# LAD_1_0.net
KiCad netlist of a schematic drawn in EAGLE
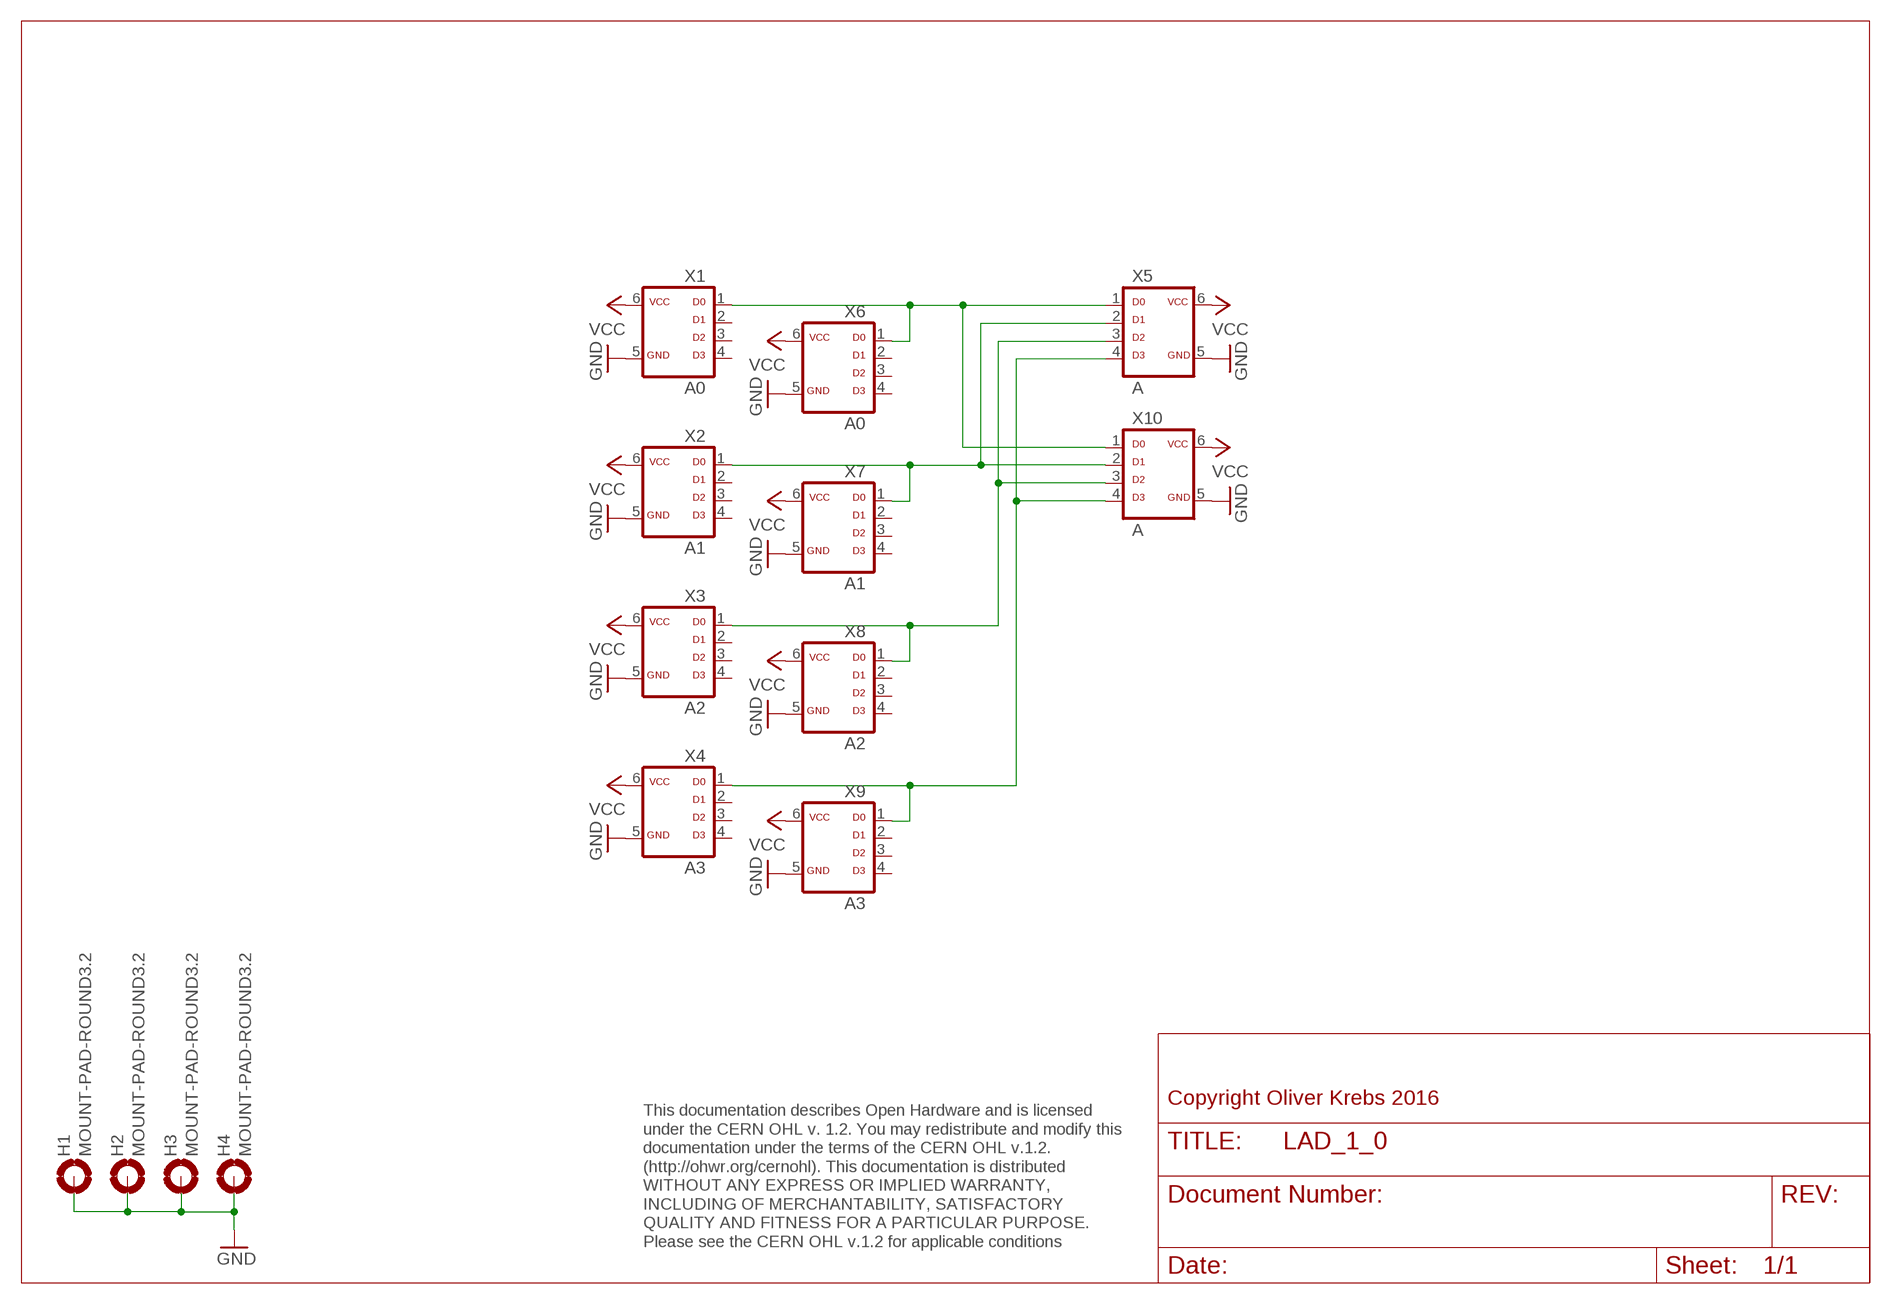
[diagram p0: schematic, sheet 1]

(export (version "E")
  (design (tool "Eeschema 10.0.6"))
  (components
    (comp (ref "H1")
      (value "MOUNT-PAD-ROUND3.2")
      (footprint "eagle-import:3,2-PAD")
      (libsource (lib "eagle-import") (part "MOUNT-PAD-ROUND3.2"))
    )
    (comp (ref "H2")
      (value "MOUNT-PAD-ROUND3.2")
      (footprint "eagle-import:3,2-PAD")
      (libsource (lib "eagle-import") (part "MOUNT-PAD-ROUND3.2"))
    )
    (comp (ref "H3")
      (value "MOUNT-PAD-ROUND3.2")
      (footprint "eagle-import:3,2-PAD")
      (libsource (lib "eagle-import") (part "MOUNT-PAD-ROUND3.2"))
    )
    (comp (ref "H4")
      (value "MOUNT-PAD-ROUND3.2")
      (footprint "eagle-import:3,2-PAD")
      (libsource (lib "eagle-import") (part "MOUNT-PAD-ROUND3.2"))
    )
    (comp (ref "X1")
      (value "A0")
      (footprint "eagle-import:ML-6")
      (libsource (lib "eagle-import") (part "ML6D"))
    )
    (comp (ref "X2")
      (value "A1")
      (footprint "eagle-import:ML-6")
      (libsource (lib "eagle-import") (part "ML6D"))
    )
    (comp (ref "X3")
      (value "A2")
      (footprint "eagle-import:ML-6")
      (libsource (lib "eagle-import") (part "ML6D"))
    )
    (comp (ref "X4")
      (value "A3")
      (footprint "eagle-import:ML-6")
      (libsource (lib "eagle-import") (part "ML6D"))
    )
    (comp (ref "X5")
      (value "A")
      (footprint "eagle-import:ML-6")
      (libsource (lib "eagle-import") (part "ML6D"))
    )
    (comp (ref "X6")
      (value "A0")
      (footprint "eagle-import:ML-6")
      (libsource (lib "eagle-import") (part "ML6D"))
    )
    (comp (ref "X7")
      (value "A1")
      (footprint "eagle-import:ML-6")
      (libsource (lib "eagle-import") (part "ML6D"))
    )
    (comp (ref "X8")
      (value "A2")
      (footprint "eagle-import:ML-6")
      (libsource (lib "eagle-import") (part "ML6D"))
    )
    (comp (ref "X9")
      (value "A3")
      (footprint "eagle-import:ML-6")
      (libsource (lib "eagle-import") (part "ML6D"))
    )
    (comp (ref "X10")
      (value "A")
      (footprint "eagle-import:ML-6")
      (libsource (lib "eagle-import") (part "ML6D"))
    )
  )
  (nets
    (net (code "1") (name "GND") (class "Default")
      (node (ref "H1") (pin "B3,2") (pinfunction "MOUNT_B3,2") (pintype "passive"))
      (node (ref "H2") (pin "B3,2") (pinfunction "MOUNT_B3,2") (pintype "passive"))
      (node (ref "H3") (pin "B3,2") (pinfunction "MOUNT_B3,2") (pintype "passive"))
      (node (ref "H4") (pin "B3,2") (pinfunction "MOUNT_B3,2") (pintype "passive"))
      (node (ref "X1") (pin "5") (pinfunction "5_5") (pintype "passive"))
      (node (ref "X10") (pin "5") (pinfunction "5_5") (pintype "passive"))
      (node (ref "X2") (pin "5") (pinfunction "5_5") (pintype "passive"))
      (node (ref "X3") (pin "5") (pinfunction "5_5") (pintype "passive"))
      (node (ref "X4") (pin "5") (pinfunction "5_5") (pintype "passive"))
      (node (ref "X5") (pin "5") (pinfunction "5_5") (pintype "passive"))
      (node (ref "X6") (pin "5") (pinfunction "5_5") (pintype "passive"))
      (node (ref "X7") (pin "5") (pinfunction "5_5") (pintype "passive"))
      (node (ref "X8") (pin "5") (pinfunction "5_5") (pintype "passive"))
      (node (ref "X9") (pin "5") (pinfunction "5_5") (pintype "passive"))
    )
    (net (code "2") (name "Net-(X1-Pad1)") (class "Default")
      (node (ref "X1") (pin "1") (pinfunction "1_1") (pintype "passive"))
      (node (ref "X10") (pin "1") (pinfunction "1_1") (pintype "passive"))
      (node (ref "X5") (pin "1") (pinfunction "1_1") (pintype "passive"))
      (node (ref "X6") (pin "1") (pinfunction "1_1") (pintype "passive"))
    )
    (net (code "3") (name "Net-(X10-Pad2)") (class "Default")
      (node (ref "X10") (pin "2") (pinfunction "2_2") (pintype "passive"))
      (node (ref "X2") (pin "1") (pinfunction "1_1") (pintype "passive"))
      (node (ref "X5") (pin "2") (pinfunction "2_2") (pintype "passive"))
      (node (ref "X7") (pin "1") (pinfunction "1_1") (pintype "passive"))
    )
    (net (code "4") (name "Net-(X10-Pad3)") (class "Default")
      (node (ref "X10") (pin "3") (pinfunction "3_3") (pintype "passive"))
      (node (ref "X3") (pin "1") (pinfunction "1_1") (pintype "passive"))
      (node (ref "X5") (pin "3") (pinfunction "3_3") (pintype "passive"))
      (node (ref "X8") (pin "1") (pinfunction "1_1") (pintype "passive"))
    )
    (net (code "5") (name "Net-(X10-Pad4)") (class "Default")
      (node (ref "X10") (pin "4") (pinfunction "4_4") (pintype "passive"))
      (node (ref "X4") (pin "1") (pinfunction "1_1") (pintype "passive"))
      (node (ref "X5") (pin "4") (pinfunction "4_4") (pintype "passive"))
      (node (ref "X9") (pin "1") (pinfunction "1_1") (pintype "passive"))
    )
    (net (code "6") (name "VCC") (class "Default")
      (node (ref "X1") (pin "6") (pinfunction "6_6") (pintype "passive"))
      (node (ref "X10") (pin "6") (pinfunction "6_6") (pintype "passive"))
      (node (ref "X2") (pin "6") (pinfunction "6_6") (pintype "passive"))
      (node (ref "X3") (pin "6") (pinfunction "6_6") (pintype "passive"))
      (node (ref "X4") (pin "6") (pinfunction "6_6") (pintype "passive"))
      (node (ref "X5") (pin "6") (pinfunction "6_6") (pintype "passive"))
      (node (ref "X6") (pin "6") (pinfunction "6_6") (pintype "passive"))
      (node (ref "X7") (pin "6") (pinfunction "6_6") (pintype "passive"))
      (node (ref "X8") (pin "6") (pinfunction "6_6") (pintype "passive"))
      (node (ref "X9") (pin "6") (pinfunction "6_6") (pintype "passive"))
    )
    (net (code "7") (name "unconnected-(X1-Pad2)") (class "Default")
      (node (ref "X1") (pin "2") (pinfunction "2_2") (pintype "passive"))
    )
    (net (code "8") (name "unconnected-(X1-Pad3)") (class "Default")
      (node (ref "X1") (pin "3") (pinfunction "3_3") (pintype "passive"))
    )
    (net (code "9") (name "unconnected-(X1-Pad4)") (class "Default")
      (node (ref "X1") (pin "4") (pinfunction "4_4") (pintype "passive"))
    )
    (net (code "10") (name "unconnected-(X2-Pad2)") (class "Default")
      (node (ref "X2") (pin "2") (pinfunction "2_2") (pintype "passive"))
    )
    (net (code "11") (name "unconnected-(X2-Pad3)") (class "Default")
      (node (ref "X2") (pin "3") (pinfunction "3_3") (pintype "passive"))
    )
    (net (code "12") (name "unconnected-(X2-Pad4)") (class "Default")
      (node (ref "X2") (pin "4") (pinfunction "4_4") (pintype "passive"))
    )
    (net (code "13") (name "unconnected-(X3-Pad2)") (class "Default")
      (node (ref "X3") (pin "2") (pinfunction "2_2") (pintype "passive"))
    )
    (net (code "14") (name "unconnected-(X3-Pad3)") (class "Default")
      (node (ref "X3") (pin "3") (pinfunction "3_3") (pintype "passive"))
    )
    (net (code "15") (name "unconnected-(X3-Pad4)") (class "Default")
      (node (ref "X3") (pin "4") (pinfunction "4_4") (pintype "passive"))
    )
    (net (code "16") (name "unconnected-(X4-Pad2)") (class "Default")
      (node (ref "X4") (pin "2") (pinfunction "2_2") (pintype "passive"))
    )
    (net (code "17") (name "unconnected-(X4-Pad3)") (class "Default")
      (node (ref "X4") (pin "3") (pinfunction "3_3") (pintype "passive"))
    )
    (net (code "18") (name "unconnected-(X4-Pad4)") (class "Default")
      (node (ref "X4") (pin "4") (pinfunction "4_4") (pintype "passive"))
    )
    (net (code "19") (name "unconnected-(X6-Pad2)") (class "Default")
      (node (ref "X6") (pin "2") (pinfunction "2_2") (pintype "passive"))
    )
    (net (code "20") (name "unconnected-(X6-Pad3)") (class "Default")
      (node (ref "X6") (pin "3") (pinfunction "3_3") (pintype "passive"))
    )
    (net (code "21") (name "unconnected-(X6-Pad4)") (class "Default")
      (node (ref "X6") (pin "4") (pinfunction "4_4") (pintype "passive"))
    )
    (net (code "22") (name "unconnected-(X7-Pad2)") (class "Default")
      (node (ref "X7") (pin "2") (pinfunction "2_2") (pintype "passive"))
    )
    (net (code "23") (name "unconnected-(X7-Pad3)") (class "Default")
      (node (ref "X7") (pin "3") (pinfunction "3_3") (pintype "passive"))
    )
    (net (code "24") (name "unconnected-(X7-Pad4)") (class "Default")
      (node (ref "X7") (pin "4") (pinfunction "4_4") (pintype "passive"))
    )
    (net (code "25") (name "unconnected-(X8-Pad2)") (class "Default")
      (node (ref "X8") (pin "2") (pinfunction "2_2") (pintype "passive"))
    )
    (net (code "26") (name "unconnected-(X8-Pad3)") (class "Default")
      (node (ref "X8") (pin "3") (pinfunction "3_3") (pintype "passive"))
    )
    (net (code "27") (name "unconnected-(X8-Pad4)") (class "Default")
      (node (ref "X8") (pin "4") (pinfunction "4_4") (pintype "passive"))
    )
    (net (code "28") (name "unconnected-(X9-Pad2)") (class "Default")
      (node (ref "X9") (pin "2") (pinfunction "2_2") (pintype "passive"))
    )
    (net (code "29") (name "unconnected-(X9-Pad3)") (class "Default")
      (node (ref "X9") (pin "3") (pinfunction "3_3") (pintype "passive"))
    )
    (net (code "30") (name "unconnected-(X9-Pad4)") (class "Default")
      (node (ref "X9") (pin "4") (pinfunction "4_4") (pintype "passive"))
    )
  )
)
